# controller_board.net
KiCad netlist of a schematic drawn in EAGLE
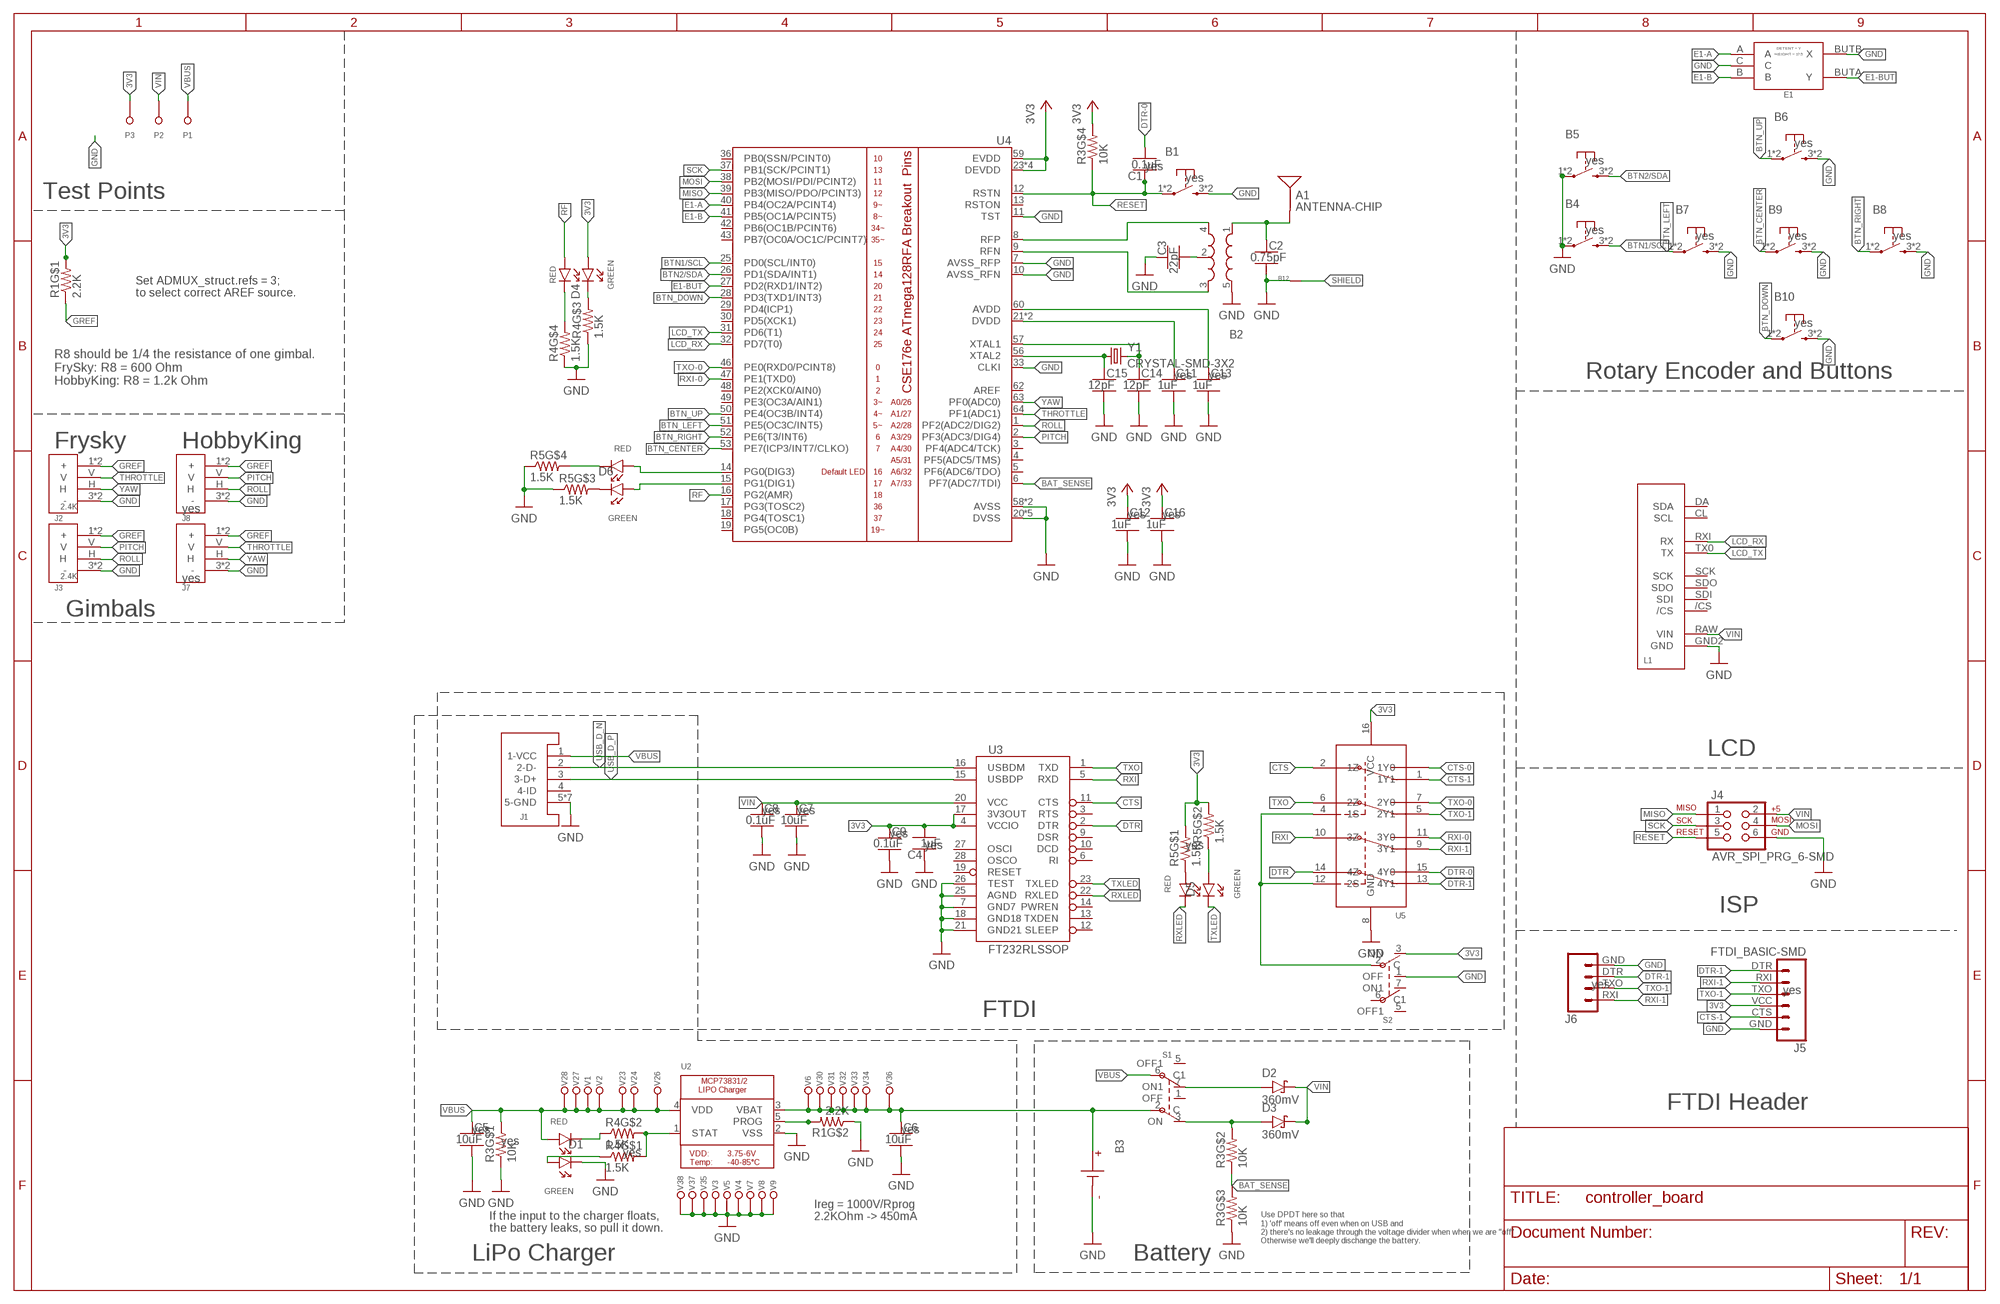
[diagram p0: schematic, sheet 1]

(export (version "E")
  (design (tool "Eeschema 10.0.6"))
  (components
    (comp (ref "A1")
      (value "ANTENNA-CHIP")
      (footprint "eagle-import:ANTENNA-CHIP")
      (fields
        (field (name "MFR") "Linx Technologies Inc.")
        (field (name "MPN") "ANT-2.45-CHP-T")
        (field (name "CREATOR") "Swanson")
        (field (name "REVIEWER") "Swanson")
      )
      (libsource (lib "eagle-import") (part "ANTENNA-CHIP"))
    )
    (comp (ref "B1")
      (value "PUSHBUTTON_-4.5X4.5")
      (footprint "eagle-import:4.5MM_TACTILE_SWITCH_TL3305AF160QG")
      (fields
        (field (name "MFR") "E-Switch")
        (field (name "MPN") "TL3305AF160QG")
        (field (name "SUBSTITUTE_OK") "yes")
        (field (name "CREATOR") "Swanson")
      )
      (libsource (lib "eagle-import") (part "PUSHBUTTON_-4.5X4.5"))
    )
    (comp (ref "B2")
      (value "BALUN0805")
      (footprint "eagle-import:BALUN")
      (fields
        (field (name "MFR") "Wurth Electronics Inc.")
        (field (name "MPN") "748421245")
        (field (name "CREATOR") "Swanson")
        (field (name "REVIEWER") "Swanson")
      )
      (libsource (lib "eagle-import") (part "BALUN0805"))
    )
    (comp (ref "B3")
      (value "BATTERY-SMD")
      (footprint "eagle-import:MOLEX-BATTERY-CONNECTOR-SMD-51005-2P")
      (fields (field (name "MFR") "UNKNOWN") (field (name "CREATOR") "Swanson"))
      (libsource (lib "eagle-import") (part "BATTERY-SMD"))
    )
    (comp (ref "B4")
      (value "PUSHBUTTON_-4.5X4.5")
      (footprint "eagle-import:4.5MM_TACTILE_SWITCH_TL3305AF160QG")
      (fields
        (field (name "MFR") "E-Switch")
        (field (name "MPN") "TL3305AF160QG")
        (field (name "SUBSTITUTE_OK") "yes")
        (field (name "CREATOR") "Swanson")
      )
      (libsource (lib "eagle-import") (part "PUSHBUTTON_-4.5X4.5"))
    )
    (comp (ref "B5")
      (value "PUSHBUTTON_-4.5X4.5")
      (footprint "eagle-import:4.5MM_TACTILE_SWITCH_TL3305AF160QG")
      (fields
        (field (name "MFR") "E-Switch")
        (field (name "MPN") "TL3305AF160QG")
        (field (name "SUBSTITUTE_OK") "yes")
        (field (name "CREATOR") "Swanson")
      )
      (libsource (lib "eagle-import") (part "PUSHBUTTON_-4.5X4.5"))
    )
    (comp (ref "B6")
      (value "PUSHBUTTON_-4.5X4.5")
      (footprint "eagle-import:4.5MM_TACTILE_SWITCH_TL3305AF160QG")
      (fields
        (field (name "MFR") "E-Switch")
        (field (name "MPN") "TL3305AF160QG")
        (field (name "SUBSTITUTE_OK") "yes")
        (field (name "CREATOR") "Swanson")
      )
      (libsource (lib "eagle-import") (part "PUSHBUTTON_-4.5X4.5"))
    )
    (comp (ref "B7")
      (value "PUSHBUTTON_-4.5X4.5")
      (footprint "eagle-import:4.5MM_TACTILE_SWITCH_TL3305AF160QG")
      (fields
        (field (name "MFR") "E-Switch")
        (field (name "MPN") "TL3305AF160QG")
        (field (name "SUBSTITUTE_OK") "yes")
        (field (name "CREATOR") "Swanson")
      )
      (libsource (lib "eagle-import") (part "PUSHBUTTON_-4.5X4.5"))
    )
    (comp (ref "B8")
      (value "PUSHBUTTON_-4.5X4.5")
      (footprint "eagle-import:4.5MM_TACTILE_SWITCH_TL3305AF160QG")
      (fields
        (field (name "MFR") "E-Switch")
        (field (name "MPN") "TL3305AF160QG")
        (field (name "SUBSTITUTE_OK") "yes")
        (field (name "CREATOR") "Swanson")
      )
      (libsource (lib "eagle-import") (part "PUSHBUTTON_-4.5X4.5"))
    )
    (comp (ref "B9")
      (value "PUSHBUTTON_-4.5X4.5")
      (footprint "eagle-import:4.5MM_TACTILE_SWITCH_TL3305AF160QG")
      (fields
        (field (name "MFR") "E-Switch")
        (field (name "MPN") "TL3305AF160QG")
        (field (name "SUBSTITUTE_OK") "yes")
        (field (name "CREATOR") "Swanson")
      )
      (libsource (lib "eagle-import") (part "PUSHBUTTON_-4.5X4.5"))
    )
    (comp (ref "B10")
      (value "PUSHBUTTON_-4.5X4.5")
      (footprint "eagle-import:4.5MM_TACTILE_SWITCH_TL3305AF160QG")
      (fields
        (field (name "MFR") "E-Switch")
        (field (name "MPN") "TL3305AF160QG")
        (field (name "SUBSTITUTE_OK") "yes")
        (field (name "CREATOR") "Swanson")
      )
      (libsource (lib "eagle-import") (part "PUSHBUTTON_-4.5X4.5"))
    )
    (comp (ref "B12")
      (value "NET_BRIDGE")
      (footprint "eagle-import:NET_BRIDGE")
      (fields (field (name "MFR") "None") (field (name "CREATOR") "Michael Gonzalez"))
      (libsource (lib "eagle-import") (part "NET_BRIDGE"))
    )
    (comp (ref "C1")
      (value "0.1uF")
      (footprint "eagle-import:CAPC1608X100")
      (fields
        (field (name "MFR") "KEMET")
        (field (name "MPN") "C0603C104K8RACTU")
        (field (name "SUBSTITUTE_OK") "yes")
        (field (name "CREATOR") "Swanson")
      )
      (libsource (lib "eagle-import") (part "CAPACITOR-NP_SMD-0603_CERAMIC-0.1UF"))
    )
    (comp (ref "C2")
      (value "0.75pF")
      (footprint "eagle-import:CAPC1608X100")
      (fields
        (field (name "MFR") "Yageo")
        (field (name "MPN") "CC0603BRNPO9BNR75")
        (field (name "CREATOR") "Swanson")
      )
      (libsource (lib "eagle-import") (part "CAPACITOR-NP_SMD-0603_CERAMIC-0.75PF"))
    )
    (comp (ref "C3")
      (value "22pF")
      (footprint "eagle-import:CAPC1608X100")
      (fields
        (field (name "MFR") "AVX Corporation")
        (field (name "MPN") "06036A220KAT2A")
        (field (name "CREATOR") "Swanson")
      )
      (libsource (lib "eagle-import") (part "CAPACITOR-NP_SMD-0603_CERAMIC-22PF"))
    )
    (comp (ref "C4")
      (value "1uF")
      (footprint "eagle-import:CAPC1608X100")
      (fields
        (field (name "MFR") "Samsung Electro-Mechanics")
        (field (name "MPN") "CL10A105KP8NNNC")
        (field (name "SUBSTITUTE_OK") "yes")
        (field (name "CREATOR") "Swanson")
      )
      (libsource (lib "eagle-import") (part "CAPACITOR-NP_SMD-0603_CERAMIC-1UF"))
    )
    (comp (ref "C5")
      (value "10uF")
      (footprint "eagle-import:CAPC1608X100")
      (fields
        (field (name "MFR") "Samsung Electro-Mechanics")
        (field (name "MPN") "CL10A106MQ8NNNC")
        (field (name "SUBSTITUTE_OK") "yes")
        (field (name "CREATOR") "Swanson")
      )
      (libsource (lib "eagle-import") (part "CAPACITOR-NP_SMD-0603_CERAMIC-10UF"))
    )
    (comp (ref "C6")
      (value "10uF")
      (footprint "eagle-import:CAPC1608X100")
      (fields
        (field (name "MFR") "Samsung Electro-Mechanics")
        (field (name "MPN") "CL10A106MQ8NNNC")
        (field (name "SUBSTITUTE_OK") "yes")
        (field (name "CREATOR") "Swanson")
      )
      (libsource (lib "eagle-import") (part "CAPACITOR-NP_SMD-0603_CERAMIC-10UF"))
    )
    (comp (ref "C7")
      (value "10uF")
      (footprint "eagle-import:CAPC1608X100")
      (fields
        (field (name "MFR") "Samsung Electro-Mechanics")
        (field (name "MPN") "CL10A106MQ8NNNC")
        (field (name "SUBSTITUTE_OK") "yes")
        (field (name "CREATOR") "Swanson")
      )
      (libsource (lib "eagle-import") (part "CAPACITOR-NP_SMD-0603_CERAMIC-10UF"))
    )
    (comp (ref "C8")
      (value "0.1uF")
      (footprint "eagle-import:CAPC1608X100")
      (fields
        (field (name "MFR") "KEMET")
        (field (name "MPN") "C0603C104K8RACTU")
        (field (name "SUBSTITUTE_OK") "yes")
        (field (name "CREATOR") "Swanson")
      )
      (libsource (lib "eagle-import") (part "CAPACITOR-NP_SMD-0603_CERAMIC-0.1UF"))
    )
    (comp (ref "C9")
      (value "0.1uF")
      (footprint "eagle-import:CAPC1608X100")
      (fields
        (field (name "MFR") "KEMET")
        (field (name "MPN") "C0603C104K8RACTU")
        (field (name "SUBSTITUTE_OK") "yes")
        (field (name "CREATOR") "Swanson")
      )
      (libsource (lib "eagle-import") (part "CAPACITOR-NP_SMD-0603_CERAMIC-0.1UF"))
    )
    (comp (ref "C11")
      (value "1uF")
      (footprint "eagle-import:CAPC1608X100")
      (fields
        (field (name "MFR") "Samsung Electro-Mechanics")
        (field (name "MPN") "CL10A105KP8NNNC")
        (field (name "SUBSTITUTE_OK") "yes")
        (field (name "CREATOR") "Swanson")
      )
      (libsource (lib "eagle-import") (part "CAPACITOR-NP_SMD-0603_CERAMIC-1UF"))
    )
    (comp (ref "C12")
      (value "1uF")
      (footprint "eagle-import:CAPC1608X100")
      (fields
        (field (name "MFR") "Samsung Electro-Mechanics")
        (field (name "MPN") "CL10A105KP8NNNC")
        (field (name "SUBSTITUTE_OK") "yes")
        (field (name "CREATOR") "Swanson")
      )
      (libsource (lib "eagle-import") (part "CAPACITOR-NP_SMD-0603_CERAMIC-1UF"))
    )
    (comp (ref "C13")
      (value "1uF")
      (footprint "eagle-import:CAPC1608X100")
      (fields
        (field (name "MFR") "Samsung Electro-Mechanics")
        (field (name "MPN") "CL10A105KP8NNNC")
        (field (name "SUBSTITUTE_OK") "yes")
        (field (name "CREATOR") "Swanson")
      )
      (libsource (lib "eagle-import") (part "CAPACITOR-NP_SMD-0603_CERAMIC-1UF"))
    )
    (comp (ref "C14")
      (value "12pF")
      (footprint "eagle-import:CAPC1608X100")
      (fields
        (field (name "MFR") "Vishay Vitramon")
        (field (name "MPN") "VJ0603A120FXQCW1BC")
        (field (name "CREATOR") "Swanson")
      )
      (libsource (lib "eagle-import") (part "CAPACITOR-NP_SMD-0603_CERAMIC-12PF"))
    )
    (comp (ref "C15")
      (value "12pF")
      (footprint "eagle-import:CAPC1608X100")
      (fields
        (field (name "MFR") "Vishay Vitramon")
        (field (name "MPN") "VJ0603A120FXQCW1BC")
        (field (name "CREATOR") "Swanson")
      )
      (libsource (lib "eagle-import") (part "CAPACITOR-NP_SMD-0603_CERAMIC-12PF"))
    )
    (comp (ref "C16")
      (value "1uF")
      (footprint "eagle-import:CAPC1608X100")
      (fields
        (field (name "MFR") "Samsung Electro-Mechanics")
        (field (name "MPN") "CL10A105KP8NNNC")
        (field (name "SUBSTITUTE_OK") "yes")
        (field (name "CREATOR") "Swanson")
      )
      (libsource (lib "eagle-import") (part "CAPACITOR-NP_SMD-0603_CERAMIC-1UF"))
    )
    (comp (ref "D1")
      (value "LED-2X-GREEN/RED-1.6X1.5MM")
      (footprint "eagle-import:LED-2X-LITE-ON-1.6MMX1.5MM")
      (fields
        (field (name "COLOR2") "GREEN")
        (field (name "COLOR1") "RED")
        (field (name "MFR") "Lite-On Inc.")
        (field (name "MPN") "LTST-C195TGKRKT")
        (field (name "CREATOR") "Swanson")
      )
      (libsource (lib "eagle-import") (part "LED-2X-GREEN/RED-1.6X1.5MM"))
    )
    (comp (ref "D2")
      (value "360mV")
      (footprint "eagle-import:SODFL3516X96")
      (fields
        (field (name "MFR") "Toshiba Semiconductor and Storage")
        (field (name "MPN") "CRS08(TE85L,Q,M)")
        (field (name "CREATOR") "Swanson")
        (field (name "REVIEWER") "Swanson")
      )
      (libsource (lib "eagle-import") (part "DIODE-SCHOTTKY_-SMD-SOD123"))
    )
    (comp (ref "D3")
      (value "360mV")
      (footprint "eagle-import:SODFL3516X96")
      (fields
        (field (name "MFR") "Toshiba Semiconductor and Storage")
        (field (name "MPN") "CRS08(TE85L,Q,M)")
        (field (name "CREATOR") "Swanson")
        (field (name "REVIEWER") "Swanson")
      )
      (libsource (lib "eagle-import") (part "DIODE-SCHOTTKY_-SMD-SOD123"))
    )
    (comp (ref "D4")
      (value "LED-2X-GREEN/RED-1.6X1.5MM")
      (footprint "eagle-import:LED-2X-LITE-ON-1.6MMX1.5MM")
      (fields
        (field (name "COLOR2") "GREEN")
        (field (name "COLOR1") "RED")
        (field (name "MFR") "Lite-On Inc.")
        (field (name "MPN") "LTST-C195TGKRKT")
        (field (name "CREATOR") "Swanson")
      )
      (libsource (lib "eagle-import") (part "LED-2X-GREEN/RED-1.6X1.5MM"))
    )
    (comp (ref "D5")
      (value "LED-2X-GREEN/RED-1.6X1.5MM")
      (footprint "eagle-import:LED-2X-LITE-ON-1.6MMX1.5MM")
      (fields
        (field (name "COLOR2") "GREEN")
        (field (name "COLOR1") "RED")
        (field (name "MFR") "Lite-On Inc.")
        (field (name "MPN") "LTST-C195TGKRKT")
        (field (name "CREATOR") "Swanson")
      )
      (libsource (lib "eagle-import") (part "LED-2X-GREEN/RED-1.6X1.5MM"))
    )
    (comp (ref "D6")
      (value "LED-2X-GREEN/RED-1.6X1.5MM")
      (footprint "eagle-import:LED-2X-LITE-ON-1.6MMX1.5MM")
      (fields
        (field (name "COLOR2") "GREEN")
        (field (name "COLOR1") "RED")
        (field (name "MFR") "Lite-On Inc.")
        (field (name "MPN") "LTST-C195TGKRKT")
        (field (name "CREATOR") "Swanson")
      )
      (libsource (lib "eagle-import") (part "LED-2X-GREEN/RED-1.6X1.5MM"))
    )
    (comp (ref "E1")
      (value "ROTARY-ENCODER-W/BUTTON-BOURNS-PEC12R-4217F")
      (footprint "eagle-import:BOURNS-PEC12R")
      (fields (field (name "DETENT") "Y") (field (name "HEIGHT") "17.5") (field (name "CREATOR") "Swanson"))
      (libsource (lib "eagle-import") (part "ROTARY-ENCODER-W/BUTTON-BOURNS-PEC12R-4217F"))
    )
    (comp (ref "J1")
      (value "USB-MICROA-AMPHENOL-10118192-0001LF")
      (footprint "eagle-import:USB-MICROA-10118192-0001LF")
      (fields
        (field (name "MFR") "Amphenol ICC (FCI)")
        (field (name "MPN") "10118192-0001LF")
        (field (name "CREATOR") "Swanson")
      )
      (libsource (lib "eagle-import") (part "USB-MICROA-AMPHENOL-10118192-0001LF"))
    )
    (comp (ref "J2")
      (value "2.4K")
      (footprint "eagle-import:JST-13-PTH")
      (fields
        (field (name "MFR") "TE Connectivity AMP Connectors")
        (field (name "MPN") "1-1735446-2")
        (field (name "CREATOR") "Swanson")
      )
      (libsource (lib "eagle-import") (part "FRSKY-GIMBAL-FRYSKY"))
    )
    (comp (ref "J3")
      (value "2.4K")
      (footprint "eagle-import:JST-13-PTH")
      (fields
        (field (name "MFR") "TE Connectivity AMP Connectors")
        (field (name "MPN") "1-1735446-2")
        (field (name "SPICEPREFIX") "E")
        (field (name "CREATOR") "Swanson")
      )
      (libsource (lib "eagle-import") (part "FRSKY-GIMBAL-FRYSKY"))
    )
    (comp (ref "J4")
      (value "AVR_SPI_PRG_6-SMD")
      (footprint "eagle-import:2X3-SMD")
      (fields
        (field (name "MFR") "Amphenol ICC (FCI)")
        (field (name "MPN") "95278-101A06LF")
        (field (name "CREATOR") "Swanson")
      )
      (libsource (lib "eagle-import") (part "AVR_SPI_PRG_6-SMD"))
    )
    (comp (ref "J5")
      (value "FTDI_BASIC-SMD")
      (footprint "eagle-import:FTDI-BASIC-SMD")
      (fields
        (field (name "MFR") "Harwin Inc.")
        (field (name "MPN") "M20-8890645")
        (field (name "SUBSTITUTE_OK") "yes")
        (field (name "CREATOR") "Swanson")
      )
      (libsource (lib "eagle-import") (part "FTDI_BASIC-SMD"))
    )
    (comp (ref "J6")
      (value "FTDI-4PIN-RIGHT-ANGLE-SMD")
      (footprint "eagle-import:HEADER-2X2-0.1IN-MALE-RIGHT-ANGLE-SMD")
      (fields
        (field (name "MFR") "Samtec Inc.")
        (field (name "MPN") "TSM-102-01-L-DH")
        (field (name "SUBSTITUTE_OK") "yes")
        (field (name "CREATOR") "Swanson")
      )
      (libsource (lib "eagle-import") (part "FTDI-4PIN-RIGHT-ANGLE-SMD"))
    )
    (comp (ref "J7")
      (value "FRSKY-GIMBAL-2X-SERVO-SMD")
      (footprint "eagle-import:2X-SERVO-SMD")
      (fields
        (field (name "MFR") "Harwin Inc.")
        (field (name "MPN") "M20-8890645")
        (field (name "SUBSTITUTE_OK") "yes")
        (field (name "CREATOR") "Swanson")
      )
      (libsource (lib "eagle-import") (part "FRSKY-GIMBAL-2X-SERVO-SMD"))
    )
    (comp (ref "J8")
      (value "FRSKY-GIMBAL-2X-SERVO-SMD")
      (footprint "eagle-import:2X-SERVO-SMD")
      (fields
        (field (name "MFR") "Harwin Inc.")
        (field (name "MPN") "M20-8890645")
        (field (name "SUBSTITUTE_OK") "yes")
        (field (name "CREATOR") "Swanson")
      )
      (libsource (lib "eagle-import") (part "FRSKY-GIMBAL-2X-SERVO-SMD"))
    )
    (comp (ref "L1")
      (value "SPARKFUN_SERLCD_SERIAL_REDUCED-SMD")
      (footprint "eagle-import:SPARKFUN_SERLCD_16X2_REDUCED_SMD")
      (fields
        (field (name "MFR") "Harwin Inc.")
        (field (name "MPN") "M20-9991045")
        (field (name "CREATOR") "Swanson")
      )
      (libsource (lib "eagle-import") (part "SPARKFUN_SERLCD_SERIAL_REDUCED-SMD"))
    )
    (comp (ref "P1")
      (value "TEST-POINT")
      (footprint "eagle-import:TEST-POINT-KEYSTONE-5000")
      (fields
        (field (name "MFR") "Keystone Electronics")
        (field (name "MPN") "5001")
        (field (name "CREATOR") "Swanson")
      )
      (libsource (lib "eagle-import") (part "TEST-POINT"))
    )
    (comp (ref "P2")
      (value "TEST-POINT")
      (footprint "eagle-import:TEST-POINT-KEYSTONE-5000")
      (fields
        (field (name "MFR") "Keystone Electronics")
        (field (name "MPN") "5001")
        (field (name "CREATOR") "Swanson")
      )
      (libsource (lib "eagle-import") (part "TEST-POINT"))
    )
    (comp (ref "P3")
      (value "TEST-POINT")
      (footprint "eagle-import:TEST-POINT-KEYSTONE-5000")
      (fields
        (field (name "MFR") "Keystone Electronics")
        (field (name "MPN") "5001")
        (field (name "CREATOR") "Swanson")
      )
      (libsource (lib "eagle-import") (part "TEST-POINT"))
    )
    (comp (ref "R1")
      (value "2.2K")
      (footprint "eagle-import:RESCAXS50P200X100X45-8")
      (fields
        (field (name "MFR") "Panasonic Electronic Components")
        (field (name "MPN") "EXB-N8V221JX")
        (field (name "SUBSTITUTE_OK") "yes")
        (field (name "CREATOR") "Swanson")
      )
      (libsource (lib "eagle-import") (part "RESISTOR-PACK-4X-2.2K"))
    )
    (comp (ref "R3")
      (value "10K")
      (footprint "eagle-import:RESCAXS50P200X100X45-8")
      (fields
        (field (name "MFR") "Panasonic Electronic Components")
        (field (name "MPN") "EXB-N8V103JX")
        (field (name "SUBSTITUTE_OK") "yes")
        (field (name "CREATOR") "Swanson")
      )
      (libsource (lib "eagle-import") (part "RESISTOR-PACK-4X-10K"))
    )
    (comp (ref "R4")
      (value "1.5K")
      (footprint "eagle-import:RESCAXS50P200X100X45-8")
      (fields
        (field (name "MFR") "Panasonic Electronic Components")
        (field (name "MPN") "EXB-N8V152JX")
        (field (name "SUBSTITUTE_OK") "yes")
        (field (name "CREATOR") "Swanson")
      )
      (libsource (lib "eagle-import") (part "RESISTOR-PACK-4X-1.5K"))
    )
    (comp (ref "R5")
      (value "1.5K")
      (footprint "eagle-import:RESCAXS50P200X100X45-8")
      (fields
        (field (name "MFR") "Panasonic Electronic Components")
        (field (name "MPN") "EXB-N8V152JX")
        (field (name "SUBSTITUTE_OK") "yes")
        (field (name "CREATOR") "Swanson")
      )
      (libsource (lib "eagle-import") (part "RESISTOR-PACK-4X-1.5K"))
    )
    (comp (ref "S1")
      (value "SWITCH-DPDT-300MA-6V-SMD")
      (footprint "eagle-import:JS202011JCQN")
      (fields
        (field (name "MFR") "C&K")
        (field (name "MPN") "JS202011JCQN")
        (field (name "CREATOR") "Swanson")
      )
      (libsource (lib "eagle-import") (part "SWITCH-DPDT-300MA-6V-SMD"))
    )
    (comp (ref "S2")
      (value "SWITCH-DPDT-300MA-6V-SMD")
      (footprint "eagle-import:JS202011JCQN")
      (fields
        (field (name "MFR") "C&K")
        (field (name "MPN") "JS202011JCQN")
        (field (name "CREATOR") "Swanson")
      )
      (libsource (lib "eagle-import") (part "SWITCH-DPDT-300MA-6V-SMD"))
    )
    (comp (ref "U2")
      (value "MCP73831T-2ACI/OT")
      (footprint "eagle-import:SOT23-5")
      (fields (field (name "MFR") "Microchip Technology") (field (name "CREATOR") "Adafruit"))
      (libsource (lib "eagle-import") (part "MCP73831/2"))
    )
    (comp (ref "U3")
      (value "FT232RLSSOP")
      (footprint "eagle-import:SSOP28DB")
      (fields
        (field (name "MFR") "FTDI")
        (field (name "MPN") "FT232RL-REEL")
        (field (name "CREATOR") "Swanson")
      )
      (libsource (lib "eagle-import") (part "FT232RLSSOP"))
    )
    (comp (ref "U4")
      (value "ATMEGA128RFA1")
      (footprint "eagle-import:QFN-64")
      (fields
        (field (name "MFR") "Microchip Technology")
        (field (name "MPN") "ATMEGA128RFA1-ZU")
        (field (name "CREATOR") "Swanson")
        (field (name "REVIEWER") "Swanson")
      )
      (libsource (lib "eagle-import") (part "ATMEGA128RFA1"))
    )
    (comp (ref "U5")
      (value "DPDT-X2")
      (footprint "eagle-import:SOP65P640X110-16")
      (fields
        (field (name "MFR") "NXP USA Inc.")
        (field (name "MPN") "NX3L2467PW,118")
        (field (name "CREATOR") "Swanson")
      )
      (libsource (lib "eagle-import") (part "DPDT-X2"))
    )
    (comp (ref "V1")
      (value "LOCKED-VIA-0.2")
      (footprint "eagle-import:VIA-0.2MM")
      (fields (field (name "MFR") "NA") (field (name "CREATOR") "Swanson"))
      (libsource (lib "eagle-import") (part "LOCKED-VIA-0.2"))
    )
    (comp (ref "V2")
      (value "LOCKED-VIA-0.2")
      (footprint "eagle-import:VIA-0.2MM")
      (fields (field (name "MFR") "NA") (field (name "CREATOR") "Swanson"))
      (libsource (lib "eagle-import") (part "LOCKED-VIA-0.2"))
    )
    (comp (ref "V3")
      (value "LOCKED-VIA-0.2")
      (footprint "eagle-import:VIA-0.2MM")
      (fields (field (name "MFR") "NA") (field (name "CREATOR") "Swanson"))
      (libsource (lib "eagle-import") (part "LOCKED-VIA-0.2"))
    )
    (comp (ref "V4")
      (value "LOCKED-VIA-0.2")
      (footprint "eagle-import:VIA-0.2MM")
      (fields (field (name "MFR") "NA") (field (name "CREATOR") "Swanson"))
      (libsource (lib "eagle-import") (part "LOCKED-VIA-0.2"))
    )
    (comp (ref "V5")
      (value "LOCKED-VIA-0.2")
      (footprint "eagle-import:VIA-0.2MM")
      (fields (field (name "MFR") "NA") (field (name "CREATOR") "Swanson"))
      (libsource (lib "eagle-import") (part "LOCKED-VIA-0.2"))
    )
    (comp (ref "V6")
      (value "LOCKED-VIA-0.2")
      (footprint "eagle-import:VIA-0.2MM")
      (fields (field (name "MFR") "NA") (field (name "CREATOR") "Swanson"))
      (libsource (lib "eagle-import") (part "LOCKED-VIA-0.2"))
    )
    (comp (ref "V7")
      (value "LOCKED-VIA-0.2")
      (footprint "eagle-import:VIA-0.2MM")
      (fields (field (name "MFR") "NA") (field (name "CREATOR") "Swanson"))
      (libsource (lib "eagle-import") (part "LOCKED-VIA-0.2"))
    )
    (comp (ref "V8")
      (value "LOCKED-VIA-0.2")
      (footprint "eagle-import:VIA-0.2MM")
      (fields (field (name "MFR") "NA") (field (name "CREATOR") "Swanson"))
      (libsource (lib "eagle-import") (part "LOCKED-VIA-0.2"))
    )
    (comp (ref "V9")
      (value "LOCKED-VIA-0.2")
      (footprint "eagle-import:VIA-0.2MM")
      (fields (field (name "MFR") "NA") (field (name "CREATOR") "Swanson"))
      (libsource (lib "eagle-import") (part "LOCKED-VIA-0.2"))
    )
    (comp (ref "V23")
      (value "LOCKED-VIA-0.2")
      (footprint "eagle-import:VIA-0.2MM")
      (fields (field (name "MFR") "NA") (field (name "CREATOR") "Swanson"))
      (libsource (lib "eagle-import") (part "LOCKED-VIA-0.2"))
    )
    (comp (ref "V24")
      (value "LOCKED-VIA-0.2")
      (footprint "eagle-import:VIA-0.2MM")
      (fields (field (name "MFR") "NA") (field (name "CREATOR") "Swanson"))
      (libsource (lib "eagle-import") (part "LOCKED-VIA-0.2"))
    )
    (comp (ref "V26")
      (value "LOCKED-VIA-0.2")
      (footprint "eagle-import:VIA-0.2MM")
      (fields (field (name "MFR") "NA") (field (name "CREATOR") "Swanson"))
      (libsource (lib "eagle-import") (part "LOCKED-VIA-0.2"))
    )
    (comp (ref "V27")
      (value "LOCKED-VIA-0.2")
      (footprint "eagle-import:VIA-0.2MM")
      (fields (field (name "MFR") "NA") (field (name "CREATOR") "Swanson"))
      (libsource (lib "eagle-import") (part "LOCKED-VIA-0.2"))
    )
    (comp (ref "V28")
      (value "LOCKED-VIA-0.2")
      (footprint "eagle-import:VIA-0.2MM")
      (fields (field (name "MFR") "NA") (field (name "CREATOR") "Swanson"))
      (libsource (lib "eagle-import") (part "LOCKED-VIA-0.2"))
    )
    (comp (ref "V30")
      (value "LOCKED-VIA-0.2")
      (footprint "eagle-import:VIA-0.2MM")
      (fields (field (name "MFR") "NA") (field (name "CREATOR") "Swanson"))
      (libsource (lib "eagle-import") (part "LOCKED-VIA-0.2"))
    )
    (comp (ref "V31")
      (value "LOCKED-VIA-0.2")
      (footprint "eagle-import:VIA-0.2MM")
      (fields (field (name "MFR") "NA") (field (name "CREATOR") "Swanson"))
      (libsource (lib "eagle-import") (part "LOCKED-VIA-0.2"))
    )
    (comp (ref "V32")
      (value "LOCKED-VIA-0.2")
      (footprint "eagle-import:VIA-0.2MM")
      (fields (field (name "MFR") "NA") (field (name "CREATOR") "Swanson"))
      (libsource (lib "eagle-import") (part "LOCKED-VIA-0.2"))
    )
    (comp (ref "V33")
      (value "LOCKED-VIA-0.2")
      (footprint "eagle-import:VIA-0.2MM")
      (fields (field (name "MFR") "NA") (field (name "CREATOR") "Swanson"))
      (libsource (lib "eagle-import") (part "LOCKED-VIA-0.2"))
    )
    (comp (ref "V34")
      (value "LOCKED-VIA-0.2")
      (footprint "eagle-import:VIA-0.2MM")
      (fields (field (name "MFR") "NA") (field (name "CREATOR") "Swanson"))
      (libsource (lib "eagle-import") (part "LOCKED-VIA-0.2"))
    )
    (comp (ref "V35")
      (value "LOCKED-VIA-0.2")
      (footprint "eagle-import:VIA-0.2MM")
      (fields (field (name "MFR") "NA") (field (name "CREATOR") "Swanson"))
      (libsource (lib "eagle-import") (part "LOCKED-VIA-0.2"))
    )
    (comp (ref "V36")
      (value "LOCKED-VIA-0.2")
      (footprint "eagle-import:VIA-0.2MM")
      (fields (field (name "MFR") "NA") (field (name "CREATOR") "Swanson"))
      (libsource (lib "eagle-import") (part "LOCKED-VIA-0.2"))
    )
    (comp (ref "V37")
      (value "LOCKED-VIA-0.2")
      (footprint "eagle-import:VIA-0.2MM")
      (fields (field (name "MFR") "NA") (field (name "CREATOR") "Swanson"))
      (libsource (lib "eagle-import") (part "LOCKED-VIA-0.2"))
    )
    (comp (ref "V38")
      (value "LOCKED-VIA-0.2")
      (footprint "eagle-import:VIA-0.2MM")
      (fields (field (name "MFR") "NA") (field (name "CREATOR") "Swanson"))
      (libsource (lib "eagle-import") (part "LOCKED-VIA-0.2"))
    )
    (comp (ref "Y1")
      (value "CRYSTAL-SMD-3X2")
      (footprint "eagle-import:OSCCC320X250X85")
      (fields
        (field (name "MFR") "Abracon LLC")
        (field (name "MPN") "ABM8-16.000MHZ-B2-T")
        (field (name "CREATOR") "Swanson")
      )
      (libsource (lib "eagle-import") (part "CRYSTAL-SMD-3X2"))
    )
  )
  (nets
    (net (code "1") (name "3V3") (class "Default")
      (node (ref "C12") (pin "1") (pinfunction "1_1") (pintype "passive"))
      (node (ref "C16") (pin "1") (pinfunction "1_1") (pintype "passive"))
      (node (ref "C4") (pin "2") (pinfunction "2_2") (pintype "passive"))
      (node (ref "C9") (pin "1") (pinfunction "1_1") (pintype "passive"))
      (node (ref "D4") (pin "A1") (pinfunction "A1_A1") (pintype "passive"))
      (node (ref "J5") (pin "VCC") (pinfunction "4_VCC") (pintype "passive"))
      (node (ref "P3") (pin "T") (pinfunction "T_T") (pintype "bidirectional"))
      (node (ref "R1") (pin "5") (pinfunction "2_5") (pintype "passive"))
      (node (ref "R3") (pin "8") (pinfunction "2_8") (pintype "passive"))
      (node (ref "R5") (pin "5") (pinfunction "2_5") (pintype "passive"))
      (node (ref "R5") (pin "6") (pinfunction "2_6") (pintype "passive"))
      (node (ref "S2") (pin "3") (pinfunction "ON_3") (pintype "bidirectional"))
      (node (ref "U3") (pin "17") (pinfunction "3V3OUT_17") (pintype "output"))
      (node (ref "U3") (pin "4") (pinfunction "VCCIO_4") (pintype "power_in"))
      (node (ref "U4") (pin "23") (pinfunction "DEVDD_23") (pintype "bidirectional"))
      (node (ref "U4") (pin "34") (pinfunction "DEVDD_34") (pintype "bidirectional"))
      (node (ref "U4") (pin "44") (pinfunction "DEVDD_44") (pintype "bidirectional"))
      (node (ref "U4") (pin "54") (pinfunction "DEVDD_54") (pintype "bidirectional"))
      (node (ref "U4") (pin "59") (pinfunction "EVDD_59") (pintype "bidirectional"))
      (node (ref "U5") (pin "16") (pinfunction "VCC_16") (pintype "bidirectional"))
    )
    (net (code "2") (name "BAT_SENSE") (class "Default")
      (node (ref "R3") (pin "3") (pinfunction "1_3") (pintype "passive"))
      (node (ref "R3") (pin "7") (pinfunction "2_7") (pintype "passive"))
      (node (ref "U4") (pin "6") (pinfunction "PF7(ADC7/TDI)_6") (pintype "bidirectional"))
    )
    (net (code "3") (name "BTN1{slash}SCL") (class "Default")
      (node (ref "B4") (pin "3") (pinfunction "2_3") (pintype "passive"))
      (node (ref "B4") (pin "4") (pinfunction "2_4") (pintype "passive"))
      (node (ref "U4") (pin "25") (pinfunction "PD0(SCL/INT0)_25") (pintype "bidirectional"))
    )
    (net (code "4") (name "BTN2{slash}SDA") (class "Default")
      (node (ref "B5") (pin "3") (pinfunction "2_3") (pintype "passive"))
      (node (ref "B5") (pin "4") (pinfunction "2_4") (pintype "passive"))
      (node (ref "U4") (pin "26") (pinfunction "PD1(SDA/INT1)_26") (pintype "bidirectional"))
    )
    (net (code "5") (name "BTN_CENTER") (class "Default")
      (node (ref "B9") (pin "1") (pinfunction "1_1") (pintype "passive"))
      (node (ref "B9") (pin "2") (pinfunction "1_2") (pintype "passive"))
      (node (ref "U4") (pin "53") (pinfunction "PE7(ICP3/INT7/CLKO)_53") (pintype "bidirectional"))
    )
    (net (code "6") (name "BTN_DOWN") (class "Default")
      (node (ref "B10") (pin "1") (pinfunction "1_1") (pintype "passive"))
      (node (ref "B10") (pin "2") (pinfunction "1_2") (pintype "passive"))
      (node (ref "U4") (pin "28") (pinfunction "PD3(TXD1/INT3)_28") (pintype "bidirectional"))
    )
    (net (code "7") (name "BTN_LEFT") (class "Default")
      (node (ref "B7") (pin "1") (pinfunction "1_1") (pintype "passive"))
      (node (ref "B7") (pin "2") (pinfunction "1_2") (pintype "passive"))
      (node (ref "U4") (pin "51") (pinfunction "PE5(OC3C/INT5)_51") (pintype "bidirectional"))
    )
    (net (code "8") (name "BTN_RIGHT") (class "Default")
      (node (ref "B8") (pin "1") (pinfunction "1_1") (pintype "passive"))
      (node (ref "B8") (pin "2") (pinfunction "1_2") (pintype "passive"))
      (node (ref "U4") (pin "52") (pinfunction "PE6(T3/INT6)_52") (pintype "bidirectional"))
    )
    (net (code "9") (name "BTN_UP") (class "Default")
      (node (ref "B6") (pin "1") (pinfunction "1_1") (pintype "passive"))
      (node (ref "B6") (pin "2") (pinfunction "1_2") (pintype "passive"))
      (node (ref "U4") (pin "50") (pinfunction "PE4(OC3B/INT4)_50") (pintype "bidirectional"))
    )
    (net (code "10") (name "CTS") (class "Default")
      (node (ref "U3") (pin "11") (pinfunction "CTS_11") (pintype "input"))
      (node (ref "U5") (pin "2") (pinfunction "1Z_2") (pintype "bidirectional"))
    )
    (net (code "11") (name "CTS-0") (class "Default")
      (node (ref "U5") (pin "3") (pinfunction "1Y0_3") (pintype "bidirectional"))
    )
    (net (code "12") (name "CTS-1") (class "Default")
      (node (ref "J5") (pin "CTS") (pinfunction "5_CTS") (pintype "passive"))
      (node (ref "U5") (pin "1") (pinfunction "1Y1_1") (pintype "bidirectional"))
    )
    (net (code "13") (name "DTR") (class "Default")
      (node (ref "U3") (pin "2") (pinfunction "DTR_2") (pintype "output"))
      (node (ref "U5") (pin "14") (pinfunction "4Z_14") (pintype "bidirectional"))
    )
    (net (code "14") (name "DTR-0") (class "Default")
      (node (ref "C1") (pin "2") (pinfunction "2_2") (pintype "passive"))
      (node (ref "U5") (pin "15") (pinfunction "4Y0_15") (pintype "bidirectional"))
    )
    (net (code "15") (name "DTR-1") (class "Default")
      (node (ref "J5") (pin "DTR") (pinfunction "1_DTR") (pintype "passive"))
      (node (ref "J6") (pin "DTR") (pinfunction "3_DTR") (pintype "bidirectional"))
      (node (ref "U5") (pin "13") (pinfunction "4Y1_13") (pintype "bidirectional"))
    )
    (net (code "16") (name "E1-A") (class "Default")
      (node (ref "E1") (pin "A") (pinfunction "A_A") (pintype "bidirectional"))
      (node (ref "U4") (pin "40") (pinfunction "PB4(OC2A/PCINT4)_40") (pintype "bidirectional"))
    )
    (net (code "17") (name "E1-B") (class "Default")
      (node (ref "E1") (pin "B") (pinfunction "B_B") (pintype "bidirectional"))
      (node (ref "U4") (pin "41") (pinfunction "PB5(OC1A/PCINT5)_41") (pintype "bidirectional"))
    )
    (net (code "18") (name "E1-BUT") (class "Default")
      (node (ref "E1") (pin "BUTA") (pinfunction "Y_BUTA") (pintype "bidirectional"))
      (node (ref "U4") (pin "27") (pinfunction "PD2(RXD1/INT2)_27") (pintype "bidirectional"))
    )
    (net (code "19") (name "GND") (class "Default")
      (node (ref "B1") (pin "3") (pinfunction "2_3") (pintype "passive"))
      (node (ref "B1") (pin "4") (pinfunction "2_4") (pintype "passive"))
      (node (ref "B10") (pin "3") (pinfunction "2_3") (pintype "passive"))
      (node (ref "B10") (pin "4") (pinfunction "2_4") (pintype "passive"))
      (node (ref "B12") (pin "P1") (pinfunction "P1_P1") (pintype "bidirectional"))
      (node (ref "B2") (pin "5") (pinfunction "GND_5") (pintype "bidirectional"))
      (node (ref "B3") (pin "G") (pinfunction "N_G") (pintype "bidirectional"))
      (node (ref "B3") (pin "G2") (pinfunction "N_G2") (pintype "bidirectional"))
      (node (ref "B3") (pin "G3") (pinfunction "N_G3") (pintype "bidirectional"))
      (node (ref "B4") (pin "1") (pinfunction "1_1") (pintype "passive"))
      (node (ref "B4") (pin "2") (pinfunction "1_2") (pintype "passive"))
      (node (ref "B5") (pin "1") (pinfunction "1_1") (pintype "passive"))
      (node (ref "B5") (pin "2") (pinfunction "1_2") (pintype "passive"))
      (node (ref "B6") (pin "3") (pinfunction "2_3") (pintype "passive"))
      (node (ref "B6") (pin "4") (pinfunction "2_4") (pintype "passive"))
      (node (ref "B7") (pin "3") (pinfunction "2_3") (pintype "passive"))
      (node (ref "B7") (pin "4") (pinfunction "2_4") (pintype "passive"))
      (node (ref "B8") (pin "3") (pinfunction "2_3") (pintype "passive"))
      (node (ref "B8") (pin "4") (pinfunction "2_4") (pintype "passive"))
      (node (ref "B9") (pin "3") (pinfunction "2_3") (pintype "passive"))
      (node (ref "B9") (pin "4") (pinfunction "2_4") (pintype "passive"))
      (node (ref "C11") (pin "2") (pinfunction "2_2") (pintype "passive"))
      (node (ref "C12") (pin "2") (pinfunction "2_2") (pintype "passive"))
      (node (ref "C13") (pin "2") (pinfunction "2_2") (pintype "passive"))
      (node (ref "C14") (pin "2") (pinfunction "2_2") (pintype "passive"))
      (node (ref "C15") (pin "2") (pinfunction "2_2") (pintype "passive"))
      (node (ref "C16") (pin "2") (pinfunction "2_2") (pintype "passive"))
      (node (ref "C2") (pin "2") (pinfunction "2_2") (pintype "passive"))
      (node (ref "C3") (pin "1") (pinfunction "1_1") (pintype "passive"))
      (node (ref "C4") (pin "1") (pinfunction "1_1") (pintype "passive"))
      (node (ref "C5") (pin "2") (pinfunction "2_2") (pintype "passive"))
      (node (ref "C6") (pin "2") (pinfunction "2_2") (pintype "passive"))
      (node (ref "C7") (pin "2") (pinfunction "2_2") (pintype "passive"))
      (node (ref "C8") (pin "2") (pinfunction "2_2") (pintype "passive"))
      (node (ref "C9") (pin "2") (pinfunction "2_2") (pintype "passive"))
      (node (ref "D1") (pin "C1") (pinfunction "C1_C1") (pintype "passive"))
      (node (ref "E1") (pin "BUTB") (pinfunction "X_BUTB") (pintype "bidirectional"))
      (node (ref "E1") (pin "C") (pinfunction "C_C") (pintype "bidirectional"))
      (node (ref "J1") (pin "10") (pinfunction "5-GND_10") (pintype "bidirectional"))
      (node (ref "J1") (pin "11") (pinfunction "5-GND_11") (pintype "bidirectional"))
      (node (ref "J1") (pin "5") (pinfunction "5-GND_5") (pintype "bidirectional"))
      (node (ref "J1") (pin "6") (pinfunction "5-GND_6") (pintype "bidirectional"))
      (node (ref "J1") (pin "7") (pinfunction "5-GND_7") (pintype "bidirectional"))
      (node (ref "J1") (pin "8") (pinfunction "5-GND_8") (pintype "bidirectional"))
      (node (ref "J1") (pin "9") (pinfunction "5-GND_9") (pintype "bidirectional"))
      (node (ref "J2") (pin "3") (pinfunction "-_3") (pintype "bidirectional"))
      (node (ref "J2") (pin "6") (pinfunction "-_6") (pintype "bidirectional"))
      (node (ref "J3") (pin "3") (pinfunction "-_3") (pintype "bidirectional"))
      (node (ref "J3") (pin "6") (pinfunction "-_6") (pintype "bidirectional"))
      (node (ref "J4") (pin "6") (pinfunction "6_6") (pintype "passive"))
      (node (ref "J5") (pin "GND") (pinfunction "6_GND") (pintype "passive"))
      (node (ref "J6") (pin "GND") (pinfunction "4_GND") (pintype "bidirectional"))
      (node (ref "J7") (pin "3") (pinfunction "-_3") (pintype "bidirectional"))
      (node (ref "J7") (pin "6") (pinfunction "-_6") (pintype "bidirectional"))
      (node (ref "J8") (pin "3") (pinfunction "-_3") (pintype "bidirectional"))
      (node (ref "J8") (pin "6") (pinfunction "-_6") (pintype "bidirectional"))
      (node (ref "L1") (pin "GND2") (pinfunction "GND_GND2") (pintype "bidirectional"))
      (node (ref "R1") (pin "3") (pinfunction "1_3") (pintype "passive"))
      (node (ref "R3") (pin "2") (pinfunction "1_2") (pintype "passive"))
      (node (ref "R3") (pin "4") (pinfunction "1_4") (pintype "passive"))
      (node (ref "R4") (pin "1") (pinfunction "1_1") (pintype "passive"))
      (node (ref "R4") (pin "2") (pinfunction "1_2") (pintype "passive"))
      (node (ref "R5") (pin "1") (pinfunction "1_1") (pintype "passive"))
      (node (ref "R5") (pin "2") (pinfunction "1_2") (pintype "passive"))
      (node (ref "S2") (pin "1") (pinfunction "OFF_1") (pintype "bidirectional"))
      (node (ref "U2") (pin "2") (pinfunction "VSS_2") (pintype "power_in"))
      (node (ref "U3") (pin "18") (pinfunction "GND18_18") (pintype "power_in"))
      (node (ref "U3") (pin "21") (pinfunction "GND21_21") (pintype "power_in"))
      (node (ref "U3") (pin "25") (pinfunction "AGND_25") (pintype "power_in"))
      (node (ref "U3") (pin "26") (pinfunction "TEST_26") (pintype "input"))
      (node (ref "U3") (pin "7") (pinfunction "GND7_7") (pintype "power_in"))
      (node (ref "U4") (pin "10") (pinfunction "AVSS_RFN_10") (pintype "bidirectional"))
      (node (ref "U4") (pin "11") (pinfunction "TST_11") (pintype "bidirectional"))
      (node (ref "U4") (pin "20") (pinfunction "DVSS_20") (pintype "bidirectional"))
      (node (ref "U4") (pin "24") (pinfunction "DVSS_24") (pintype "bidirectional"))
      (node (ref "U4") (pin "33") (pinfunction "CLKI_33") (pintype "bidirectional"))
      (node (ref "U4") (pin "35") (pinfunction "DVSS_35") (pintype "bidirectional"))
      (node (ref "U4") (pin "45") (pinfunction "DVSS_45") (pintype "bidirectional"))
      (node (ref "U4") (pin "55") (pinfunction "DVSS_55") (pintype "bidirectional"))
      (node (ref "U4") (pin "58") (pinfunction "AVSS_58") (pintype "bidirectional"))
      (node (ref "U4") (pin "61") (pinfunction "AVSS_61") (pintype "bidirectional"))
      (node (ref "U4") (pin "7") (pinfunction "AVSS_RFP_7") (pintype "bidirectional"))
      (node (ref "U5") (pin "8") (pinfunction "GND_8") (pintype "bidirectional"))
      (node (ref "V3") (pin "P1") (pinfunction "N_P1") (pintype "bidirectional"))
      (node (ref "V35") (pin "P1") (pinfunction "N_P1") (pintype "bidirectional"))
      (node (ref "V37") (pin "P1") (pinfunction "N_P1") (pintype "bidirectional"))
      (node (ref "V38") (pin "P1") (pinfunction "N_P1") (pintype "bidirectional"))
      (node (ref "V4") (pin "P1") (pinfunction "N_P1") (pintype "bidirectional"))
      (node (ref "V5") (pin "P1") (pinfunction "N_P1") (pintype "bidirectional"))
      (node (ref "V7") (pin "P1") (pinfunction "N_P1") (pintype "bidirectional"))
      (node (ref "V8") (pin "P1") (pinfunction "N_P1") (pintype "bidirectional"))
      (node (ref "V9") (pin "P1") (pinfunction "N_P1") (pintype "bidirectional"))
    )
    (net (code "20") (name "GREF") (class "Default")
      (node (ref "J2") (pin "1") (pinfunction "+_1") (pintype "bidirectional"))
      (node (ref "J2") (pin "4") (pinfunction "+_4") (pintype "bidirectional"))
      (node (ref "J3") (pin "1") (pinfunction "+_1") (pintype "bidirectional"))
      (node (ref "J3") (pin "4") (pinfunction "+_4") (pintype "bidirectional"))
      (node (ref "J7") (pin "1") (pinfunction "+_1") (pintype "bidirectional"))
      (node (ref "J7") (pin "4") (pinfunction "+_4") (pintype "bidirectional"))
      (node (ref "J8") (pin "1") (pinfunction "+_1") (pintype "bidirectional"))
      (node (ref "J8") (pin "4") (pinfunction "+_4") (pintype "bidirectional"))
      (node (ref "R1") (pin "4") (pinfunction "1_4") (pintype "passive"))
    )
    (net (code "21") (name "LCD_RX") (class "Default")
      (node (ref "L1") (pin "RXI") (pinfunction "RX_RXI") (pintype "bidirectional"))
      (node (ref "U4") (pin "32") (pinfunction "PD7(T0)_32") (pintype "bidirectional"))
    )
    (net (code "22") (name "LCD_TX") (class "Default")
      (node (ref "L1") (pin "TX0") (pinfunction "TX_TX0") (pintype "bidirectional"))
      (node (ref "U4") (pin "31") (pinfunction "PD6(T1)_31") (pintype "bidirectional"))
    )
    (net (code "23") (name "MISO") (class "Default")
      (node (ref "J4") (pin "1") (pinfunction "1_1") (pintype "passive"))
      (node (ref "U4") (pin "39") (pinfunction "PB3(MISO/PDO/PCINT3)_39") (pintype "bidirectional"))
    )
    (net (code "24") (name "MOSI") (class "Default")
      (node (ref "J4") (pin "4") (pinfunction "4_4") (pintype "passive"))
      (node (ref "U4") (pin "38") (pinfunction "PB2(MOSI/PDI/PCINT2)_38") (pintype "bidirectional"))
    )
    (net (code "25") (name "Net-(A1-SIGNAL)") (class "Default")
      (node (ref "A1") (pin "FEED") (pinfunction "SIGNAL_FEED") (pintype "bidirectional"))
      (node (ref "B2") (pin "1") (pinfunction "IN_1") (pintype "bidirectional"))
      (node (ref "C2") (pin "1") (pinfunction "1_1") (pintype "passive"))
    )
    (net (code "26") (name "Net-(B2-GND-Pad2)") (class "Default")
      (node (ref "B2") (pin "2") (pinfunction "GND_2") (pintype "bidirectional"))
      (node (ref "C3") (pin "2") (pinfunction "2_2") (pintype "passive"))
    )
    (net (code "27") (name "Net-(B2-OUT1)") (class "Default")
      (node (ref "B2") (pin "4") (pinfunction "OUT1_4") (pintype "bidirectional"))
      (node (ref "U4") (pin "8") (pinfunction "RFP_8") (pintype "bidirectional"))
    )
    (net (code "28") (name "Net-(B2-OUT2)") (class "Default")
      (node (ref "B2") (pin "3") (pinfunction "OUT2_3") (pintype "bidirectional"))
      (node (ref "U4") (pin "9") (pinfunction "RFN_9") (pintype "bidirectional"))
    )
    (net (code "29") (name "Net-(C11-Pad1)") (class "Default")
      (node (ref "C11") (pin "1") (pinfunction "1_1") (pintype "passive"))
      (node (ref "U4") (pin "21") (pinfunction "DVDD_21") (pintype "bidirectional"))
      (node (ref "U4") (pin "22") (pinfunction "DVDD_22") (pintype "bidirectional"))
    )
    (net (code "30") (name "Net-(D2-A)") (class "Default")
      (node (ref "D2") (pin "2") (pinfunction "A_2") (pintype "passive"))
      (node (ref "S1") (pin "7") (pinfunction "ON1_7") (pintype "bidirectional"))
    )
    (net (code "31") (name "Net-(D3-A)") (class "Default")
      (node (ref "D3") (pin "2") (pinfunction "A_2") (pintype "passive"))
      (node (ref "R3") (pin "6") (pinfunction "2_6") (pintype "passive"))
      (node (ref "S1") (pin "3") (pinfunction "ON_3") (pintype "bidirectional"))
    )
    (net (code "32") (name "Net-(R1B-2)") (class "Default")
      (node (ref "R1") (pin "6") (pinfunction "2_6") (pintype "passive"))
      (node (ref "U2") (pin "5") (pinfunction "PROG_5") (pintype "input"))
    )
    (net (code "33") (name "Net-(R4A-1)") (class "Default")
      (node (ref "D1") (pin "A1") (pinfunction "A1_A1") (pintype "passive"))
      (node (ref "R4") (pin "4") (pinfunction "1_4") (pintype "passive"))
    )
    (net (code "34") (name "Net-(R4A-2)") (class "Default")
      (node (ref "R4") (pin "5") (pinfunction "2_5") (pintype "passive"))
      (node (ref "R4") (pin "6") (pinfunction "2_6") (pintype "passive"))
      (node (ref "U2") (pin "1") (pinfunction "STAT_1") (pintype "output"))
    )
    (net (code "35") (name "Net-(R4B-1)") (class "Default")
      (node (ref "D1") (pin "C2") (pinfunction "C2_C2") (pintype "passive"))
      (node (ref "R4") (pin "3") (pinfunction "1_3") (pintype "passive"))
    )
    (net (code "36") (name "Net-(R4C-2)") (class "Default")
      (node (ref "D4") (pin "C1") (pinfunction "C1_C1") (pintype "passive"))
      (node (ref "R4") (pin "7") (pinfunction "2_7") (pintype "passive"))
    )
    (net (code "37") (name "Net-(R4D-2)") (class "Default")
      (node (ref "D4") (pin "C2") (pinfunction "C2_C2") (pintype "passive"))
      (node (ref "R4") (pin "8") (pinfunction "2_8") (pintype "passive"))
    )
    (net (code "38") (name "Net-(R5A-1)") (class "Default")
      (node (ref "D5") (pin "A2") (pinfunction "A2_A2") (pintype "passive"))
      (node (ref "R5") (pin "4") (pinfunction "1_4") (pintype "passive"))
    )
    (net (code "39") (name "Net-(R5B-1)") (class "Default")
      (node (ref "D5") (pin "A1") (pinfunction "A1_A1") (pintype "passive"))
      (node (ref "R5") (pin "3") (pinfunction "1_3") (pintype "passive"))
    )
    (net (code "40") (name "Net-(R5C-2)") (class "Default")
      (node (ref "D6") (pin "C1") (pinfunction "C1_C1") (pintype "passive"))
      (node (ref "R5") (pin "7") (pinfunction "2_7") (pintype "passive"))
    )
    (net (code "41") (name "Net-(R5D-2)") (class "Default")
      (node (ref "D6") (pin "C2") (pinfunction "C2_C2") (pintype "passive"))
      (node (ref "R5") (pin "8") (pinfunction "2_8") (pintype "passive"))
    )
    (net (code "42") (name "Net-(S1-C)") (class "Default")
      (node (ref "B3") (pin "P") (pinfunction "P_P") (pintype "bidirectional"))
      (node (ref "C6") (pin "1") (pinfunction "1_1") (pintype "passive"))
      (node (ref "S1") (pin "2") (pinfunction "C_2") (pintype "bidirectional"))
      (node (ref "U2") (pin "3") (pinfunction "VBAT_3") (pintype "power_in"))
      (node (ref "V30") (pin "P1") (pinfunction "N_P1") (pintype "bidirectional"))
      (node (ref "V31") (pin "P1") (pinfunction "N_P1") (pintype "bidirectional"))
      (node (ref "V32") (pin "P1") (pinfunction "N_P1") (pintype "bidirectional"))
      (node (ref "V33") (pin "P1") (pinfunction "N_P1") (pintype "bidirectional"))
      (node (ref "V34") (pin "P1") (pinfunction "N_P1") (pintype "bidirectional"))
      (node (ref "V36") (pin "P1") (pinfunction "N_P1") (pintype "bidirectional"))
      (node (ref "V6") (pin "P1") (pinfunction "N_P1") (pintype "bidirectional"))
    )
    (net (code "43") (name "Net-(S2-C)") (class "Default")
      (node (ref "S2") (pin "2") (pinfunction "C_2") (pintype "bidirectional"))
      (node (ref "U5") (pin "12") (pinfunction "2S_12") (pintype "bidirectional"))
      (node (ref "U5") (pin "4") (pinfunction "1S_4") (pintype "bidirectional"))
    )
    (net (code "44") (name "Net-(U4-AVDD)") (class "Default")
      (node (ref "C13") (pin "1") (pinfunction "1_1") (pintype "passive"))
      (node (ref "U4") (pin "60") (pinfunction "AVDD_60") (pintype "bidirectional"))
    )
    (net (code "45") (name "Net-(U4-PG0(DIG3))") (class "Default")
      (node (ref "D6") (pin "A2") (pinfunction "A2_A2") (pintype "passive"))
      (node (ref "U4") (pin "14") (pinfunction "PG0(DIG3)_14") (pintype "bidirectional"))
    )
    (net (code "46") (name "Net-(U4-PG1(DIG1))") (class "Default")
      (node (ref "D6") (pin "A1") (pinfunction "A1_A1") (pintype "passive"))
      (node (ref "U4") (pin "15") (pinfunction "PG1(DIG1)_15") (pintype "bidirectional"))
    )
    (net (code "47") (name "Net-(U4-XTAL1)") (class "Default")
      (node (ref "C14") (pin "1") (pinfunction "1_1") (pintype "passive"))
      (node (ref "U4") (pin "57") (pinfunction "XTAL1_57") (pintype "bidirectional"))
      (node (ref "Y1") (pin "3") (pinfunction "2_3") (pintype "passive"))
    )
    (net (code "48") (name "Net-(U4-XTAL2)") (class "Default")
      (node (ref "C15") (pin "1") (pinfunction "1_1") (pintype "passive"))
      (node (ref "U4") (pin "56") (pinfunction "XTAL2_56") (pintype "bidirectional"))
      (node (ref "Y1") (pin "1") (pinfunction "1_1") (pintype "passive"))
    )
    (net (code "49") (name "PITCH") (class "Default")
      (node (ref "J3") (pin "V") (pinfunction "V_V") (pintype "bidirectional"))
      (node (ref "J8") (pin "V") (pinfunction "V_V") (pintype "bidirectional"))
      (node (ref "U4") (pin "2") (pinfunction "PF3(ADC3/DIG4)_2") (pintype "bidirectional"))
    )
    (net (code "50") (name "RESET") (class "Default")
      (node (ref "B1") (pin "1") (pinfunction "1_1") (pintype "passive"))
      (node (ref "B1") (pin "2") (pinfunction "1_2") (pintype "passive"))
      (node (ref "C1") (pin "1") (pinfunction "1_1") (pintype "passive"))
      (node (ref "J4") (pin "5") (pinfunction "5_5") (pintype "passive"))
      (node (ref "R3") (pin "1") (pinfunction "1_1") (pintype "passive"))
      (node (ref "U4") (pin "12") (pinfunction "RSTN_12") (pintype "bidirectional"))
    )
    (net (code "51") (name "RF") (class "Default")
      (node (ref "D4") (pin "A2") (pinfunction "A2_A2") (pintype "passive"))
      (node (ref "U4") (pin "16") (pinfunction "PG2(AMR)_16") (pintype "bidirectional"))
    )
    (net (code "52") (name "ROLL") (class "Default")
      (node (ref "J3") (pin "H") (pinfunction "H_H") (pintype "bidirectional"))
      (node (ref "J8") (pin "H") (pinfunction "H_H") (pintype "bidirectional"))
      (node (ref "U4") (pin "1") (pinfunction "PF2(ADC2/DIG2)_1") (pintype "bidirectional"))
    )
    (net (code "53") (name "RXI") (class "Default")
      (node (ref "U3") (pin "5") (pinfunction "RXD_5") (pintype "input"))
      (node (ref "U5") (pin "10") (pinfunction "3Z_10") (pintype "bidirectional"))
    )
    (net (code "54") (name "RXI-0") (class "Default")
      (node (ref "U4") (pin "47") (pinfunction "PE1(TXD0)_47") (pintype "bidirectional"))
      (node (ref "U5") (pin "11") (pinfunction "3Y0_11") (pintype "bidirectional"))
    )
    (net (code "55") (name "RXI-1") (class "Default")
      (node (ref "J5") (pin "RXI") (pinfunction "2_RXI") (pintype "passive"))
      (node (ref "J6") (pin "RXI") (pinfunction "1_RXI") (pintype "bidirectional"))
      (node (ref "U5") (pin "9") (pinfunction "3Y1_9") (pintype "bidirectional"))
    )
    (net (code "56") (name "RXLED") (class "Default")
      (node (ref "D5") (pin "C2") (pinfunction "C2_C2") (pintype "passive"))
      (node (ref "U3") (pin "22") (pinfunction "RXLED_22") (pintype "input"))
    )
    (net (code "57") (name "SCK") (class "Default")
      (node (ref "J4") (pin "3") (pinfunction "3_3") (pintype "passive"))
      (node (ref "U4") (pin "37") (pinfunction "PB1(SCK/PCINT1)_37") (pintype "bidirectional"))
    )
    (net (code "58") (name "SHIELD") (class "Default")
      (node (ref "B12") (pin "P2") (pinfunction "P2_P2") (pintype "bidirectional"))
    )
    (net (code "59") (name "THROTTLE") (class "Default")
      (node (ref "J2") (pin "V") (pinfunction "V_V") (pintype "bidirectional"))
      (node (ref "J7") (pin "V") (pinfunction "V_V") (pintype "bidirectional"))
      (node (ref "U4") (pin "64") (pinfunction "PF1(ADC1)_64") (pintype "bidirectional"))
    )
    (net (code "60") (name "TXLED") (class "Default")
      (node (ref "D5") (pin "C1") (pinfunction "C1_C1") (pintype "passive"))
      (node (ref "U3") (pin "23") (pinfunction "TXLED_23") (pintype "input"))
    )
    (net (code "61") (name "TXO") (class "Default")
      (node (ref "U3") (pin "1") (pinfunction "TXD_1") (pintype "output"))
      (node (ref "U5") (pin "6") (pinfunction "2Z_6") (pintype "bidirectional"))
    )
    (net (code "62") (name "TXO-0") (class "Default")
      (node (ref "U4") (pin "46") (pinfunction "PE0(RXD0/PCINT8)_46") (pintype "bidirectional"))
      (node (ref "U5") (pin "7") (pinfunction "2Y0_7") (pintype "bidirectional"))
    )
    (net (code "63") (name "TXO-1") (class "Default")
      (node (ref "J5") (pin "TXO") (pinfunction "3_TXO") (pintype "passive"))
      (node (ref "J6") (pin "TXO") (pinfunction "2_TXO") (pintype "bidirectional"))
      (node (ref "U5") (pin "5") (pinfunction "2Y1_5") (pintype "bidirectional"))
    )
    (net (code "64") (name "USB_D_N") (class "Default")
      (node (ref "J1") (pin "2") (pinfunction "2-D-_2") (pintype "bidirectional"))
      (node (ref "U3") (pin "16") (pinfunction "USBDM_16") (pintype "bidirectional"))
    )
    (net (code "65") (name "USB_D_P") (class "Default")
      (node (ref "J1") (pin "3") (pinfunction "3-D+_3") (pintype "bidirectional"))
      (node (ref "U3") (pin "15") (pinfunction "USBDP_15") (pintype "bidirectional"))
    )
    (net (code "66") (name "VBUS") (class "Default")
      (node (ref "C5") (pin "1") (pinfunction "1_1") (pintype "passive"))
      (node (ref "D1") (pin "A2") (pinfunction "A2_A2") (pintype "passive"))
      (node (ref "J1") (pin "1") (pinfunction "1-VCC_1") (pintype "bidirectional"))
      (node (ref "P1") (pin "T") (pinfunction "T_T") (pintype "bidirectional"))
      (node (ref "R3") (pin "5") (pinfunction "2_5") (pintype "passive"))
      (node (ref "S1") (pin "6") (pinfunction "C1_6") (pintype "bidirectional"))
      (node (ref "U2") (pin "4") (pinfunction "VDD_4") (pintype "power_in"))
      (node (ref "V1") (pin "P1") (pinfunction "N_P1") (pintype "bidirectional"))
      (node (ref "V2") (pin "P1") (pinfunction "N_P1") (pintype "bidirectional"))
      (node (ref "V23") (pin "P1") (pinfunction "N_P1") (pintype "bidirectional"))
      (node (ref "V24") (pin "P1") (pinfunction "N_P1") (pintype "bidirectional"))
      (node (ref "V26") (pin "P1") (pinfunction "N_P1") (pintype "bidirectional"))
      (node (ref "V27") (pin "P1") (pinfunction "N_P1") (pintype "bidirectional"))
      (node (ref "V28") (pin "P1") (pinfunction "N_P1") (pintype "bidirectional"))
    )
    (net (code "67") (name "VIN") (class "Default")
      (node (ref "C7") (pin "1") (pinfunction "1_1") (pintype "passive"))
      (node (ref "C8") (pin "1") (pinfunction "1_1") (pintype "passive"))
      (node (ref "D2") (pin "1") (pinfunction "C_1") (pintype "passive"))
      (node (ref "D3") (pin "1") (pinfunction "C_1") (pintype "passive"))
      (node (ref "J4") (pin "2") (pinfunction "2_2") (pintype "passive"))
      (node (ref "L1") (pin "RAW") (pinfunction "VIN_RAW") (pintype "bidirectional"))
      (node (ref "P2") (pin "T") (pinfunction "T_T") (pintype "bidirectional"))
      (node (ref "U3") (pin "20") (pinfunction "VCC_20") (pintype "power_in"))
    )
    (net (code "68") (name "YAW") (class "Default")
      (node (ref "J2") (pin "H") (pinfunction "H_H") (pintype "bidirectional"))
      (node (ref "J7") (pin "H") (pinfunction "H_H") (pintype "bidirectional"))
      (node (ref "U4") (pin "63") (pinfunction "PF0(ADC0)_63") (pintype "bidirectional"))
    )
    (net (code "69") (name "unconnected-(J1-4-ID-Pad4)") (class "Default")
      (node (ref "J1") (pin "4") (pinfunction "4-ID_4") (pintype "bidirectional"))
    )
    (net (code "70") (name "unconnected-(L1-PadSCK)") (class "Default")
      (node (ref "L1") (pin "SCK") (pinfunction "SCK_SCK") (pintype "bidirectional"))
    )
    (net (code "71") (name "unconnected-(L1-PadSDI)") (class "Default")
      (node (ref "L1") (pin "SDI") (pinfunction "SDI_SDI") (pintype "bidirectional"))
    )
    (net (code "72") (name "unconnected-(L1-PadSDO)") (class "Default")
      (node (ref "L1") (pin "SDO") (pinfunction "SDO_SDO") (pintype "bidirectional"))
    )
    (net (code "73") (name "unconnected-(L1-Pad{slash}CS)") (class "Default")
      (node (ref "L1") (pin "/CS") (pinfunction "/CS_/CS") (pintype "bidirectional"))
    )
    (net (code "74") (name "unconnected-(L1-SCL-PadCL)") (class "Default")
      (node (ref "L1") (pin "CL") (pinfunction "SCL_CL") (pintype "bidirectional"))
    )
    (net (code "75") (name "unconnected-(L1-SDA-PadDA)") (class "Default")
      (node (ref "L1") (pin "DA") (pinfunction "SDA_DA") (pintype "bidirectional"))
    )
    (net (code "76") (name "unconnected-(S1-OFF-Pad1)") (class "Default")
      (node (ref "S1") (pin "1") (pinfunction "OFF_1") (pintype "bidirectional"))
    )
    (net (code "77") (name "unconnected-(S1-OFF1-Pad5)") (class "Default")
      (node (ref "S1") (pin "5") (pinfunction "OFF1_5") (pintype "bidirectional"))
    )
    (net (code "78") (name "unconnected-(S2-C1-Pad6)") (class "Default")
      (node (ref "S2") (pin "6") (pinfunction "C1_6") (pintype "bidirectional"))
    )
    (net (code "79") (name "unconnected-(S2-OFF1-Pad5)") (class "Default")
      (node (ref "S2") (pin "5") (pinfunction "OFF1_5") (pintype "bidirectional"))
    )
    (net (code "80") (name "unconnected-(S2-ON1-Pad7)") (class "Default")
      (node (ref "S2") (pin "7") (pinfunction "ON1_7") (pintype "bidirectional"))
    )
    (net (code "81") (name "unconnected-(U3-DCD-Pad10)") (class "Default")
      (node (ref "U3") (pin "10") (pinfunction "DCD_10") (pintype "input"))
    )
    (net (code "82") (name "unconnected-(U3-DSR-Pad9)") (class "Default")
      (node (ref "U3") (pin "9") (pinfunction "DSR_9") (pintype "input"))
    )
    (net (code "83") (name "unconnected-(U3-OSCI-Pad27)") (class "Default")
      (node (ref "U3") (pin "27") (pinfunction "OSCI_27") (pintype "input"))
    )
    (net (code "84") (name "unconnected-(U3-OSCO-Pad28)") (class "Default")
      (node (ref "U3") (pin "28") (pinfunction "OSCO_28") (pintype "output"))
    )
    (net (code "85") (name "unconnected-(U3-PWREN-Pad14)") (class "Default")
      (node (ref "U3") (pin "14") (pinfunction "PWREN_14") (pintype "input"))
    )
    (net (code "86") (name "unconnected-(U3-RESET-Pad19)") (class "Default")
      (node (ref "U3") (pin "19") (pinfunction "RESET_19") (pintype "input"))
    )
    (net (code "87") (name "unconnected-(U3-RI-Pad6)") (class "Default")
      (node (ref "U3") (pin "6") (pinfunction "RI_6") (pintype "input"))
    )
    (net (code "88") (name "unconnected-(U3-RTS-Pad3)") (class "Default")
      (node (ref "U3") (pin "3") (pinfunction "RTS_3") (pintype "output"))
    )
    (net (code "89") (name "unconnected-(U3-SLEEP-Pad12)") (class "Default")
      (node (ref "U3") (pin "12") (pinfunction "SLEEP_12") (pintype "input"))
    )
    (net (code "90") (name "unconnected-(U3-TXDEN-Pad13)") (class "Default")
      (node (ref "U3") (pin "13") (pinfunction "TXDEN_13") (pintype "input"))
    )
    (net (code "91") (name "unconnected-(U4-AREF-Pad62)") (class "Default")
      (node (ref "U4") (pin "62") (pinfunction "AREF_62") (pintype "bidirectional"))
    )
    (net (code "92") (name "unconnected-(U4-PB0(SSN{slash}PCINT0)-Pad36)") (class "Default")
      (node (ref "U4") (pin "36") (pinfunction "PB0(SSN/PCINT0)_36") (pintype "bidirectional"))
    )
    (net (code "93") (name "unconnected-(U4-PB6(OC1B{slash}PCINT6)-Pad42)") (class "Default")
      (node (ref "U4") (pin "42") (pinfunction "PB6(OC1B/PCINT6)_42") (pintype "bidirectional"))
    )
    (net (code "94") (name "unconnected-(U4-PB7(OC0A{slash}OC1C{slash}PCINT7)-Pad43)") (class "Default")
      (node (ref "U4") (pin "43") (pinfunction "PB7(OC0A/OC1C/PCINT7)_43") (pintype "bidirectional"))
    )
    (net (code "95") (name "unconnected-(U4-PD4(ICP1)-Pad29)") (class "Default")
      (node (ref "U4") (pin "29") (pinfunction "PD4(ICP1)_29") (pintype "bidirectional"))
    )
    (net (code "96") (name "unconnected-(U4-PD5(XCK1)-Pad30)") (class "Default")
      (node (ref "U4") (pin "30") (pinfunction "PD5(XCK1)_30") (pintype "bidirectional"))
    )
    (net (code "97") (name "unconnected-(U4-PE2(XCK0{slash}AIN0)-Pad48)") (class "Default")
      (node (ref "U4") (pin "48") (pinfunction "PE2(XCK0/AIN0)_48") (pintype "bidirectional"))
    )
    (net (code "98") (name "unconnected-(U4-PE3(OC3A{slash}AIN1)-Pad49)") (class "Default")
      (node (ref "U4") (pin "49") (pinfunction "PE3(OC3A/AIN1)_49") (pintype "bidirectional"))
    )
    (net (code "99") (name "unconnected-(U4-PF4(ADC4{slash}TCK)-Pad3)") (class "Default")
      (node (ref "U4") (pin "3") (pinfunction "PF4(ADC4/TCK)_3") (pintype "bidirectional"))
    )
    (net (code "100") (name "unconnected-(U4-PF5(ADC5{slash}TMS)-Pad4)") (class "Default")
      (node (ref "U4") (pin "4") (pinfunction "PF5(ADC5/TMS)_4") (pintype "bidirectional"))
    )
    (net (code "101") (name "unconnected-(U4-PF6(ADC6{slash}TDO)-Pad5)") (class "Default")
      (node (ref "U4") (pin "5") (pinfunction "PF6(ADC6/TDO)_5") (pintype "bidirectional"))
    )
    (net (code "102") (name "unconnected-(U4-PG3(TOSC2)-Pad17)") (class "Default")
      (node (ref "U4") (pin "17") (pinfunction "PG3(TOSC2)_17") (pintype "bidirectional"))
    )
    (net (code "103") (name "unconnected-(U4-PG4(TOSC1)-Pad18)") (class "Default")
      (node (ref "U4") (pin "18") (pinfunction "PG4(TOSC1)_18") (pintype "bidirectional"))
    )
    (net (code "104") (name "unconnected-(U4-PG5(OC0B)-Pad19)") (class "Default")
      (node (ref "U4") (pin "19") (pinfunction "PG5(OC0B)_19") (pintype "bidirectional"))
    )
    (net (code "105") (name "unconnected-(U4-RSTON-Pad13)") (class "Default")
      (node (ref "U4") (pin "13") (pinfunction "RSTON_13") (pintype "bidirectional"))
    )
  )
)
